# pic_circuit.net
KiCad netlist of a schematic drawn in EAGLE
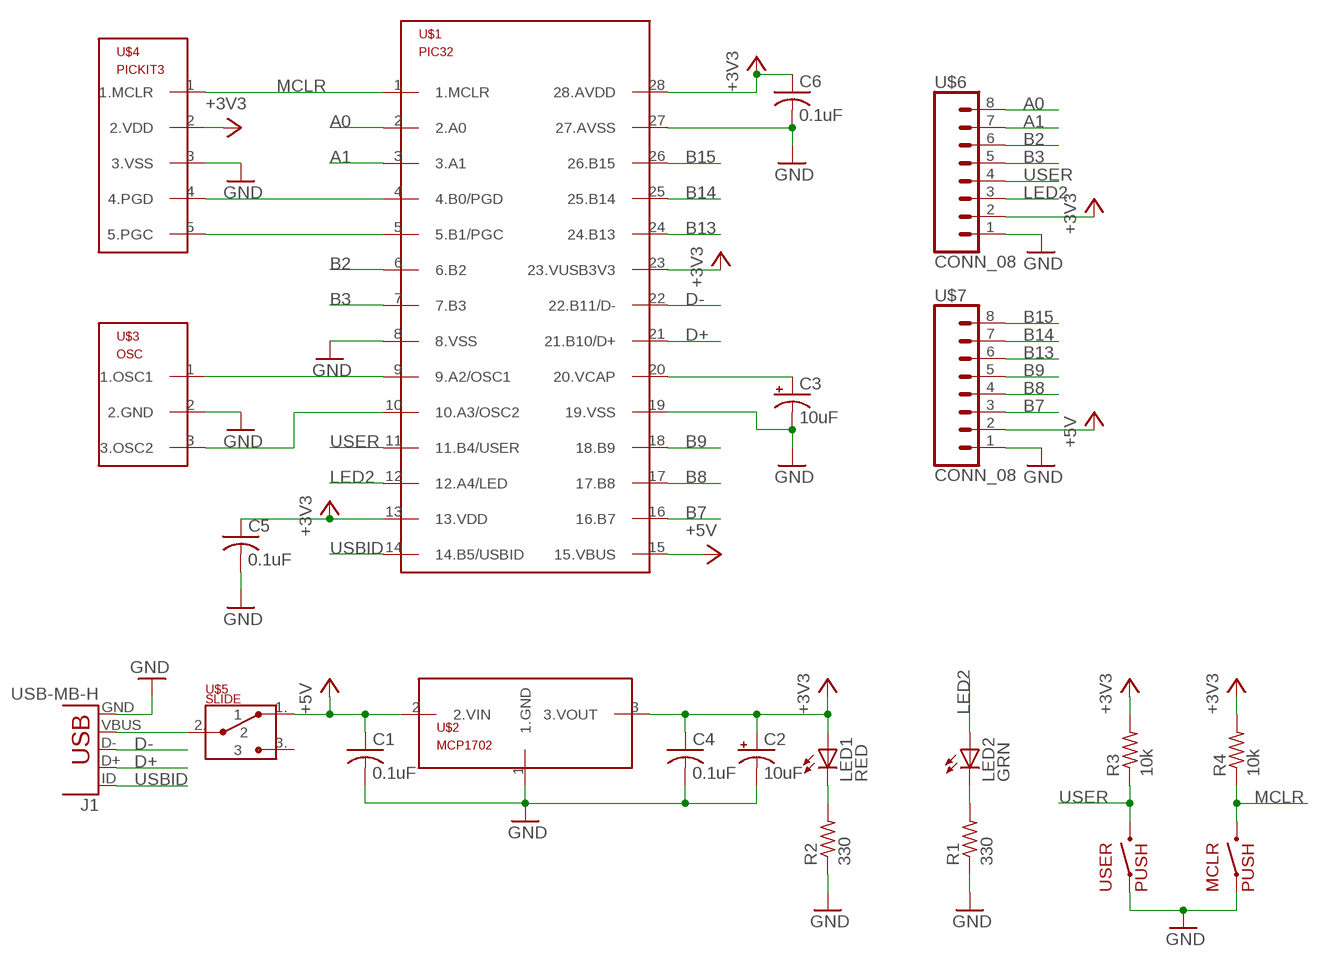
[diagram p0: schematic, sheet 1]

(export (version "E")
  (design (tool "Eeschema 10.0.6"))
  (components
    (comp (ref "C1")
      (value "0.1uF")
      (footprint "eagle-import:C025-025X050")
      (libsource (lib "eagle-import") (part "C-US025-025X050"))
    )
    (comp (ref "C2")
      (value "10uF")
      (footprint "eagle-import:B45181B")
      (libsource (lib "eagle-import") (part "CPOL-USB45181B"))
    )
    (comp (ref "C3")
      (value "10uF")
      (footprint "eagle-import:B45181B")
      (libsource (lib "eagle-import") (part "CPOL-USB45181B"))
    )
    (comp (ref "C4")
      (value "0.1uF")
      (footprint "eagle-import:C025-025X050")
      (libsource (lib "eagle-import") (part "C-US025-025X050"))
    )
    (comp (ref "C5")
      (value "0.1uF")
      (footprint "eagle-import:C025-025X050")
      (libsource (lib "eagle-import") (part "C-US025-025X050"))
    )
    (comp (ref "C6")
      (value "0.1uF")
      (footprint "eagle-import:C025-025X050")
      (libsource (lib "eagle-import") (part "C-US025-025X050"))
    )
    (comp (ref "J1")
      (value "USB-MB-H")
      (footprint "eagle-import:USB-MB-H")
      (libsource (lib "eagle-import") (part "USB-MB-H"))
    )
    (comp (ref "LED1")
      (value "RED")
      (footprint "eagle-import:LED3MM")
      (libsource (lib "eagle-import") (part "LED3MM"))
    )
    (comp (ref "LED2")
      (value "GRN")
      (footprint "eagle-import:LED3MM")
      (libsource (lib "eagle-import") (part "LED3MM"))
    )
    (comp (ref "MCLR")
      (value "PUSH")
      (footprint "eagle-import:PUSHBUTTON")
      (libsource (lib "eagle-import") (part "PUSH"))
    )
    (comp (ref "R1")
      (value "330")
      (footprint "eagle-import:0207_10")
      (libsource (lib "eagle-import") (part "R-US_0207/10"))
    )
    (comp (ref "R2")
      (value "330")
      (footprint "eagle-import:0207_10")
      (libsource (lib "eagle-import") (part "R-US_0207/10"))
    )
    (comp (ref "R3")
      (value "10k")
      (footprint "eagle-import:0207_10")
      (libsource (lib "eagle-import") (part "R-US_0207/10"))
    )
    (comp (ref "R4")
      (value "10k")
      (footprint "eagle-import:0207_10")
      (libsource (lib "eagle-import") (part "R-US_0207/10"))
    )
    (comp (ref "U$1")
      (value "PIC32")
      (footprint "eagle-import:DIL28-3")
      (libsource (lib "eagle-import") (part "PIC32MX250F128B"))
    )
    (comp (ref "U$2")
      (value "MCP1702")
      (footprint "eagle-import:TO92")
      (libsource (lib "eagle-import") (part "MCP1702"))
    )
    (comp (ref "U$3")
      (value "OSC")
      (footprint "eagle-import:OSCILLATOR")
      (libsource (lib "eagle-import") (part "OSC"))
    )
    (comp (ref "U$4")
      (value "PICKIT3")
      (footprint "eagle-import:1X05")
      (libsource (lib "eagle-import") (part "PICKIT3"))
    )
    (comp (ref "U$5")
      (value "SLIDE")
      (footprint "eagle-import:SLIDE-SWITCH")
      (libsource (lib "eagle-import") (part "SLIDE"))
    )
    (comp (ref "U$6")
      (value "CONN_08")
      (footprint "eagle-import:1X08")
      (libsource (lib "eagle-import") (part "CONN_08"))
    )
    (comp (ref "U$7")
      (value "CONN_08")
      (footprint "eagle-import:1X08")
      (libsource (lib "eagle-import") (part "CONN_08"))
    )
    (comp (ref "USER")
      (value "PUSH")
      (footprint "eagle-import:PUSHBUTTON")
      (libsource (lib "eagle-import") (part "PUSH"))
    )
  )
  (nets
    (net (code "1") (name "+3V3") (class "Default")
      (node (ref "C2") (pin "+") (pinfunction "+_+") (pintype "passive"))
      (node (ref "C4") (pin "1") (pinfunction "1_1") (pintype "passive"))
      (node (ref "C5") (pin "1") (pinfunction "1_1") (pintype "passive"))
      (node (ref "C6") (pin "1") (pinfunction "1_1") (pintype "passive"))
      (node (ref "LED1") (pin "A") (pinfunction "A_A") (pintype "passive"))
      (node (ref "R3") (pin "2") (pinfunction "2_2") (pintype "passive"))
      (node (ref "R4") (pin "2") (pinfunction "2_2") (pintype "passive"))
      (node (ref "U$1") (pin "13") (pinfunction "13.VDD_13") (pintype "bidirectional"))
      (node (ref "U$1") (pin "23") (pinfunction "23.VUSB3V3_23") (pintype "bidirectional"))
      (node (ref "U$1") (pin "28") (pinfunction "28.AVDD_28") (pintype "bidirectional"))
      (node (ref "U$2") (pin "3") (pinfunction "3.VOUT_3") (pintype "bidirectional"))
      (node (ref "U$4") (pin "2") (pinfunction "2.VDD_2") (pintype "bidirectional"))
      (node (ref "U$6") (pin "2") (pinfunction "2_2") (pintype "passive"))
    )
    (net (code "2") (name "+5V") (class "Default")
      (node (ref "C1") (pin "1") (pinfunction "1_1") (pintype "passive"))
      (node (ref "U$1") (pin "15") (pinfunction "15.VBUS_15") (pintype "bidirectional"))
      (node (ref "U$2") (pin "2") (pinfunction "2.VIN_2") (pintype "bidirectional"))
      (node (ref "U$5") (pin "1.") (pinfunction "1_1.") (pintype "bidirectional"))
      (node (ref "U$7") (pin "2") (pinfunction "2_2") (pintype "passive"))
    )
    (net (code "3") (name "/A0") (class "Default")
      (node (ref "U$1") (pin "2") (pinfunction "2.A0_2") (pintype "bidirectional"))
      (node (ref "U$6") (pin "8") (pinfunction "8_8") (pintype "passive"))
    )
    (net (code "4") (name "/A1") (class "Default")
      (node (ref "U$1") (pin "3") (pinfunction "3.A1_3") (pintype "bidirectional"))
      (node (ref "U$6") (pin "7") (pinfunction "7_7") (pintype "passive"))
    )
    (net (code "5") (name "/B2") (class "Default")
      (node (ref "U$1") (pin "6") (pinfunction "6.B2_6") (pintype "bidirectional"))
      (node (ref "U$6") (pin "6") (pinfunction "6_6") (pintype "passive"))
    )
    (net (code "6") (name "/B3") (class "Default")
      (node (ref "U$1") (pin "7") (pinfunction "7.B3_7") (pintype "bidirectional"))
      (node (ref "U$6") (pin "5") (pinfunction "5_5") (pintype "passive"))
    )
    (net (code "7") (name "/B7") (class "Default")
      (node (ref "U$1") (pin "16") (pinfunction "16.B7_16") (pintype "bidirectional"))
      (node (ref "U$7") (pin "3") (pinfunction "3_3") (pintype "passive"))
    )
    (net (code "8") (name "/B8") (class "Default")
      (node (ref "U$1") (pin "17") (pinfunction "17.B8_17") (pintype "bidirectional"))
      (node (ref "U$7") (pin "4") (pinfunction "4_4") (pintype "passive"))
    )
    (net (code "9") (name "/B9") (class "Default")
      (node (ref "U$1") (pin "18") (pinfunction "18.B9_18") (pintype "bidirectional"))
      (node (ref "U$7") (pin "5") (pinfunction "5_5") (pintype "passive"))
    )
    (net (code "10") (name "/B13") (class "Default")
      (node (ref "U$1") (pin "24") (pinfunction "24.B13_24") (pintype "bidirectional"))
      (node (ref "U$7") (pin "6") (pinfunction "6_6") (pintype "passive"))
    )
    (net (code "11") (name "/B14") (class "Default")
      (node (ref "U$1") (pin "25") (pinfunction "25.B14_25") (pintype "bidirectional"))
      (node (ref "U$7") (pin "7") (pinfunction "7_7") (pintype "passive"))
    )
    (net (code "12") (name "/B15") (class "Default")
      (node (ref "U$1") (pin "26") (pinfunction "26.B15_26") (pintype "bidirectional"))
      (node (ref "U$7") (pin "8") (pinfunction "8_8") (pintype "passive"))
    )
    (net (code "13") (name "/D+") (class "Default")
      (node (ref "J1") (pin "D+") (pinfunction "D+_D+") (pintype "bidirectional"))
      (node (ref "U$1") (pin "21") (pinfunction "21.B10/D+_21") (pintype "bidirectional"))
    )
    (net (code "14") (name "/D-") (class "Default")
      (node (ref "J1") (pin "D-") (pinfunction "D-_D-") (pintype "bidirectional"))
      (node (ref "U$1") (pin "22") (pinfunction "22.B11/D-_22") (pintype "bidirectional"))
    )
    (net (code "15") (name "/LED2") (class "Default")
      (node (ref "LED2") (pin "A") (pinfunction "A_A") (pintype "passive"))
      (node (ref "U$1") (pin "12") (pinfunction "12.A4/LED_12") (pintype "bidirectional"))
      (node (ref "U$6") (pin "3") (pinfunction "3_3") (pintype "passive"))
    )
    (net (code "16") (name "/MCLR") (class "Default")
      (node (ref "MCLR") (pin "2") (pinfunction "2_2") (pintype "bidirectional"))
      (node (ref "R4") (pin "1") (pinfunction "1_1") (pintype "passive"))
      (node (ref "U$1") (pin "1") (pinfunction "1.MCLR_1") (pintype "bidirectional"))
      (node (ref "U$4") (pin "1") (pinfunction "1.MCLR_1") (pintype "bidirectional"))
    )
    (net (code "17") (name "/USBID") (class "Default")
      (node (ref "J1") (pin "ID") (pinfunction "ID_ID") (pintype "bidirectional"))
      (node (ref "U$1") (pin "14") (pinfunction "14.B5/USBID_14") (pintype "bidirectional"))
    )
    (net (code "18") (name "/USER") (class "Default")
      (node (ref "R3") (pin "1") (pinfunction "1_1") (pintype "passive"))
      (node (ref "U$1") (pin "11") (pinfunction "11.B4/USER_11") (pintype "bidirectional"))
      (node (ref "U$6") (pin "4") (pinfunction "4_4") (pintype "passive"))
      (node (ref "USER") (pin "2") (pinfunction "2_2") (pintype "bidirectional"))
    )
    (net (code "19") (name "GND") (class "Default")
      (node (ref "C1") (pin "2") (pinfunction "2_2") (pintype "passive"))
      (node (ref "C2") (pin "-") (pinfunction "-_-") (pintype "passive"))
      (node (ref "C3") (pin "-") (pinfunction "-_-") (pintype "passive"))
      (node (ref "C4") (pin "2") (pinfunction "2_2") (pintype "passive"))
      (node (ref "C5") (pin "2") (pinfunction "2_2") (pintype "passive"))
      (node (ref "C6") (pin "2") (pinfunction "2_2") (pintype "passive"))
      (node (ref "J1") (pin "GND") (pinfunction "GND_GND") (pintype "bidirectional"))
      (node (ref "MCLR") (pin "1") (pinfunction "1_1") (pintype "bidirectional"))
      (node (ref "R1") (pin "1") (pinfunction "1_1") (pintype "passive"))
      (node (ref "R2") (pin "1") (pinfunction "1_1") (pintype "passive"))
      (node (ref "U$1") (pin "19") (pinfunction "19.VSS_19") (pintype "bidirectional"))
      (node (ref "U$1") (pin "27") (pinfunction "27.AVSS_27") (pintype "bidirectional"))
      (node (ref "U$1") (pin "8") (pinfunction "8.VSS_8") (pintype "bidirectional"))
      (node (ref "U$2") (pin "1") (pinfunction "1.GND_1") (pintype "bidirectional"))
      (node (ref "U$3") (pin "2") (pinfunction "2.GND_2") (pintype "bidirectional"))
      (node (ref "U$4") (pin "3") (pinfunction "3.VSS_3") (pintype "bidirectional"))
      (node (ref "U$6") (pin "1") (pinfunction "1_1") (pintype "passive"))
      (node (ref "U$7") (pin "1") (pinfunction "1_1") (pintype "passive"))
      (node (ref "USER") (pin "1") (pinfunction "1_1") (pintype "bidirectional"))
    )
    (net (code "20") (name "Net-(LED1-C)") (class "Default")
      (node (ref "LED1") (pin "K") (pinfunction "C_K") (pintype "passive"))
      (node (ref "R2") (pin "2") (pinfunction "2_2") (pintype "passive"))
    )
    (net (code "21") (name "Net-(LED2-C)") (class "Default")
      (node (ref "LED2") (pin "K") (pinfunction "C_K") (pintype "passive"))
      (node (ref "R1") (pin "2") (pinfunction "2_2") (pintype "passive"))
    )
    (net (code "22") (name "Net-(U$1-4.B0{slash}PGD)") (class "Default")
      (node (ref "U$1") (pin "4") (pinfunction "4.B0/PGD_4") (pintype "bidirectional"))
      (node (ref "U$4") (pin "4") (pinfunction "4.PGD_4") (pintype "bidirectional"))
    )
    (net (code "23") (name "Net-(U$1-5.B1{slash}PGC)") (class "Default")
      (node (ref "U$1") (pin "5") (pinfunction "5.B1/PGC_5") (pintype "bidirectional"))
      (node (ref "U$4") (pin "5") (pinfunction "5.PGC_5") (pintype "bidirectional"))
    )
    (net (code "24") (name "Net-(U$1-9.A2{slash}OSC1)") (class "Default")
      (node (ref "U$1") (pin "9") (pinfunction "9.A2/OSC1_9") (pintype "bidirectional"))
      (node (ref "U$3") (pin "1") (pinfunction "1.OSC1_1") (pintype "bidirectional"))
    )
    (net (code "25") (name "Net-(U$1-10.A3{slash}OSC2)") (class "Default")
      (node (ref "U$1") (pin "10") (pinfunction "10.A3/OSC2_10") (pintype "bidirectional"))
      (node (ref "U$3") (pin "3") (pinfunction "3.OSC2_3") (pintype "bidirectional"))
    )
    (net (code "26") (name "Net-(U$1-20.VCAP)") (class "Default")
      (node (ref "C3") (pin "+") (pinfunction "+_+") (pintype "passive"))
      (node (ref "U$1") (pin "20") (pinfunction "20.VCAP_20") (pintype "bidirectional"))
    )
    (net (code "27") (name "Net-(U$5-2)") (class "Default")
      (node (ref "J1") (pin "VBUS") (pinfunction "VBUS_VBUS") (pintype "bidirectional"))
      (node (ref "U$5") (pin "2.") (pinfunction "2_2.") (pintype "bidirectional"))
    )
    (net (code "28") (name "unconnected-(U$5-3-Pad3.)") (class "Default")
      (node (ref "U$5") (pin "3.") (pinfunction "3_3.") (pintype "bidirectional"))
    )
  )
)
